# Dual_Power.net
KiCad netlist of a schematic drawn in Altium Designer
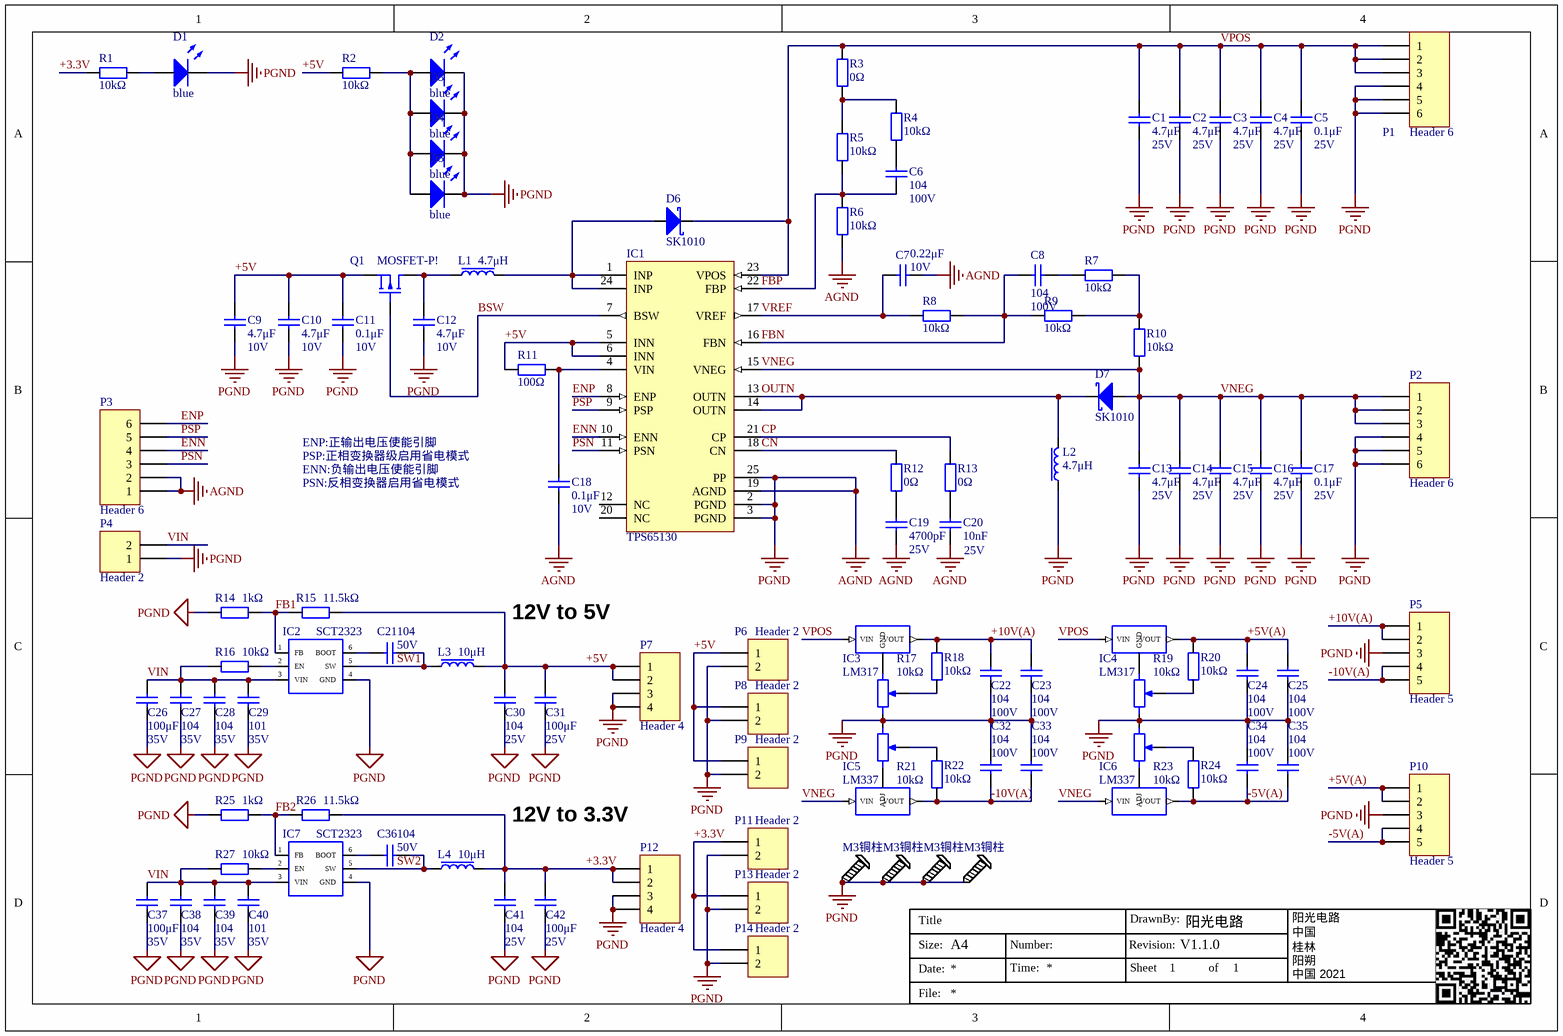
[diagram p0: Dual_Power.SchDoc]

(export (version "E")
  (design (tool "Eeschema 10.0.6"))
  (components
    (comp (ref "C1")
      (value "叠层陶瓷电容")
      (footprint "C0603")
      (description "无极性电容")
      (fields (field (name "CAPACITY") "4.7μF") (field (name "VOLTAGE") "25V"))
      (libsource (lib "原理图库") (part "104"))
    )
    (comp (ref "C2")
      (value "叠层陶瓷电容")
      (footprint "C0603")
      (description "无极性电容")
      (fields (field (name "CAPACITY") "4.7μF") (field (name "VOLTAGE") "25V"))
      (libsource (lib "原理图库") (part "104"))
    )
    (comp (ref "C3")
      (value "叠层陶瓷电容")
      (footprint "C0603")
      (description "无极性电容")
      (fields (field (name "CAPACITY") "4.7μF") (field (name "VOLTAGE") "25V"))
      (libsource (lib "原理图库") (part "104"))
    )
    (comp (ref "C4")
      (value "叠层陶瓷电容")
      (footprint "C0603")
      (description "无极性电容")
      (fields (field (name "CAPACITY") "4.7μF") (field (name "VOLTAGE") "25V"))
      (libsource (lib "原理图库") (part "104"))
    )
    (comp (ref "C5")
      (value "叠层陶瓷电容")
      (footprint "C0603")
      (description "无极性电容")
      (fields (field (name "CAPACITY") "0.1μF") (field (name "VOLTAGE") "25V"))
      (libsource (lib "原理图库") (part "104"))
    )
    (comp (ref "C6")
      (value "叠层陶瓷电容")
      (footprint "C0603")
      (description "无极性电容")
      (fields (field (name "CAPACITY") "104") (field (name "VOLTAGE") "100V"))
      (libsource (lib "原理图库") (part "104"))
    )
    (comp (ref "C7")
      (value "叠层陶瓷电容")
      (footprint "C0603")
      (description "无极性电容")
      (fields (field (name "CAPACITY") "0.22μF") (field (name "VOLTAGE") "10V"))
      (libsource (lib "原理图库") (part "104"))
    )
    (comp (ref "C8")
      (value "叠层陶瓷电容")
      (footprint "C0603")
      (description "无极性电容")
      (fields (field (name "CAPACITY") "104") (field (name "VOLTAGE") "100V"))
      (libsource (lib "原理图库") (part "104"))
    )
    (comp (ref "C9")
      (value "叠层陶瓷电容")
      (footprint "C0603")
      (description "无极性电容")
      (fields (field (name "CAPACITY") "4.7μF") (field (name "VOLTAGE") "10V"))
      (libsource (lib "原理图库") (part "104"))
    )
    (comp (ref "C10")
      (value "叠层陶瓷电容")
      (footprint "C0603")
      (description "无极性电容")
      (fields (field (name "CAPACITY") "4.7μF") (field (name "VOLTAGE") "10V"))
      (libsource (lib "原理图库") (part "104"))
    )
    (comp (ref "C11")
      (value "叠层陶瓷电容")
      (footprint "C0603")
      (description "无极性电容")
      (fields (field (name "CAPACITY") "0.1μF") (field (name "VOLTAGE") "10V"))
      (libsource (lib "原理图库") (part "104"))
    )
    (comp (ref "C12")
      (value "叠层陶瓷电容")
      (footprint "C0603")
      (description "无极性电容")
      (fields (field (name "CAPACITY") "4.7μF") (field (name "VOLTAGE") "10V"))
      (libsource (lib "原理图库") (part "104"))
    )
    (comp (ref "C13")
      (value "叠层陶瓷电容")
      (footprint "C0603")
      (description "无极性电容")
      (fields (field (name "CAPACITY") "4.7μF") (field (name "VOLTAGE") "25V"))
      (libsource (lib "原理图库") (part "104"))
    )
    (comp (ref "C14")
      (value "叠层陶瓷电容")
      (footprint "C0603")
      (description "无极性电容")
      (fields (field (name "CAPACITY") "4.7μF") (field (name "VOLTAGE") "25V"))
      (libsource (lib "原理图库") (part "104"))
    )
    (comp (ref "C15")
      (value "叠层陶瓷电容")
      (footprint "C0603")
      (description "无极性电容")
      (fields (field (name "CAPACITY") "4.7μF") (field (name "VOLTAGE") "25V"))
      (libsource (lib "原理图库") (part "104"))
    )
    (comp (ref "C16")
      (value "叠层陶瓷电容")
      (footprint "C0603")
      (description "无极性电容")
      (fields (field (name "CAPACITY") "4.7μF") (field (name "VOLTAGE") "25V"))
      (libsource (lib "原理图库") (part "104"))
    )
    (comp (ref "C17")
      (value "叠层陶瓷电容")
      (footprint "C0603")
      (description "无极性电容")
      (fields (field (name "CAPACITY") "0.1μF") (field (name "VOLTAGE") "25V"))
      (libsource (lib "原理图库") (part "104"))
    )
    (comp (ref "C18")
      (value "叠层陶瓷电容")
      (footprint "C0603")
      (description "无极性电容")
      (fields (field (name "CAPACITY") "0.1μF") (field (name "VOLTAGE") "10V"))
      (libsource (lib "原理图库") (part "104"))
    )
    (comp (ref "C19")
      (value "叠层陶瓷电容")
      (footprint "C0603")
      (description "无极性电容")
      (fields (field (name "CAPACITY") "4700pF") (field (name "VOLTAGE") "25V"))
      (libsource (lib "原理图库") (part "104"))
    )
    (comp (ref "C20")
      (value "叠层陶瓷电容")
      (footprint "C0603")
      (description "无极性电容")
      (fields (field (name "CAPACITY") "10nF") (field (name "VOLTAGE") "25V"))
      (libsource (lib "原理图库") (part "104"))
    )
    (comp (ref "C21")
      (value "叠层陶瓷电容")
      (footprint "C0603")
      (description "无极性电容")
      (fields (field (name "CAPACITY") "104") (field (name "VOLTAGE") "50V"))
      (libsource (lib "原理图库") (part "104"))
    )
    (comp (ref "C22")
      (value "叠层陶瓷电容")
      (footprint "C0603")
      (description "无极性电容")
      (fields (field (name "CAPACITY") "104") (field (name "VOLTAGE") "100V"))
      (libsource (lib "原理图库") (part "104"))
    )
    (comp (ref "C23")
      (value "叠层陶瓷电容")
      (footprint "C0603")
      (description "无极性电容")
      (fields (field (name "CAPACITY") "104") (field (name "VOLTAGE") "100V"))
      (libsource (lib "原理图库") (part "104"))
    )
    (comp (ref "C24")
      (value "叠层陶瓷电容")
      (footprint "C0603")
      (description "无极性电容")
      (fields (field (name "CAPACITY") "104") (field (name "VOLTAGE") "100V"))
      (libsource (lib "原理图库") (part "104"))
    )
    (comp (ref "C25")
      (value "叠层陶瓷电容")
      (footprint "C0603")
      (description "无极性电容")
      (fields (field (name "CAPACITY") "104") (field (name "VOLTAGE") "100V"))
      (libsource (lib "原理图库") (part "104"))
    )
    (comp (ref "C26")
      (value "叠层陶瓷电容")
      (footprint "C0603")
      (description "无极性电容")
      (fields (field (name "CAPACITY") "100μF") (field (name "VOLTAGE") "35V"))
      (libsource (lib "原理图库") (part "104"))
    )
    (comp (ref "C27")
      (value "叠层陶瓷电容")
      (footprint "C0603")
      (description "无极性电容")
      (fields (field (name "CAPACITY") "104") (field (name "VOLTAGE") "35V"))
      (libsource (lib "原理图库") (part "104"))
    )
    (comp (ref "C28")
      (value "叠层陶瓷电容")
      (footprint "C0603")
      (description "无极性电容")
      (fields (field (name "CAPACITY") "104") (field (name "VOLTAGE") "35V"))
      (libsource (lib "原理图库") (part "104"))
    )
    (comp (ref "C29")
      (value "叠层陶瓷电容")
      (footprint "C0603")
      (description "无极性电容")
      (fields (field (name "CAPACITY") "101") (field (name "VOLTAGE") "35V"))
      (libsource (lib "原理图库") (part "104"))
    )
    (comp (ref "C30")
      (value "叠层陶瓷电容")
      (footprint "C0603")
      (description "无极性电容")
      (fields (field (name "CAPACITY") "104") (field (name "VOLTAGE") "25V"))
      (libsource (lib "原理图库") (part "104"))
    )
    (comp (ref "C31")
      (value "叠层陶瓷电容")
      (footprint "C0603")
      (description "无极性电容")
      (fields (field (name "CAPACITY") "100μF") (field (name "VOLTAGE") "25V"))
      (libsource (lib "原理图库") (part "104"))
    )
    (comp (ref "C32")
      (value "叠层陶瓷电容")
      (footprint "C0603")
      (description "无极性电容")
      (fields (field (name "CAPACITY") "104") (field (name "VOLTAGE") "100V"))
      (libsource (lib "原理图库") (part "104"))
    )
    (comp (ref "C33")
      (value "叠层陶瓷电容")
      (footprint "C0603")
      (description "无极性电容")
      (fields (field (name "CAPACITY") "104") (field (name "VOLTAGE") "100V"))
      (libsource (lib "原理图库") (part "104"))
    )
    (comp (ref "C34")
      (value "叠层陶瓷电容")
      (footprint "C0603")
      (description "无极性电容")
      (fields (field (name "CAPACITY") "104") (field (name "VOLTAGE") "100V"))
      (libsource (lib "原理图库") (part "104"))
    )
    (comp (ref "C35")
      (value "叠层陶瓷电容")
      (footprint "C0603")
      (description "无极性电容")
      (fields (field (name "CAPACITY") "104") (field (name "VOLTAGE") "100V"))
      (libsource (lib "原理图库") (part "104"))
    )
    (comp (ref "C36")
      (value "叠层陶瓷电容")
      (footprint "C0603")
      (description "无极性电容")
      (fields (field (name "CAPACITY") "104") (field (name "VOLTAGE") "50V"))
      (libsource (lib "原理图库") (part "104"))
    )
    (comp (ref "C37")
      (value "叠层陶瓷电容")
      (footprint "C0603")
      (description "无极性电容")
      (fields (field (name "CAPACITY") "100μF") (field (name "VOLTAGE") "35V"))
      (libsource (lib "原理图库") (part "104"))
    )
    (comp (ref "C38")
      (value "叠层陶瓷电容")
      (footprint "C0603")
      (description "无极性电容")
      (fields (field (name "CAPACITY") "104") (field (name "VOLTAGE") "35V"))
      (libsource (lib "原理图库") (part "104"))
    )
    (comp (ref "C39")
      (value "叠层陶瓷电容")
      (footprint "C0603")
      (description "无极性电容")
      (fields (field (name "CAPACITY") "104") (field (name "VOLTAGE") "35V"))
      (libsource (lib "原理图库") (part "104"))
    )
    (comp (ref "C40")
      (value "叠层陶瓷电容")
      (footprint "C0603")
      (description "无极性电容")
      (fields (field (name "CAPACITY") "101") (field (name "VOLTAGE") "35V"))
      (libsource (lib "原理图库") (part "104"))
    )
    (comp (ref "C41")
      (value "叠层陶瓷电容")
      (footprint "C0603")
      (description "无极性电容")
      (fields (field (name "CAPACITY") "104") (field (name "VOLTAGE") "25V"))
      (libsource (lib "原理图库") (part "104"))
    )
    (comp (ref "C42")
      (value "叠层陶瓷电容")
      (footprint "C0603")
      (description "无极性电容")
      (fields (field (name "CAPACITY") "100μF") (field (name "VOLTAGE") "25V"))
      (libsource (lib "原理图库") (part "104"))
    )
    (comp (ref "D1")
      (value "LED")
      (footprint "LED 0603")
      (fields (field (name "TYPE") "blue"))
      (libsource (lib "原理图库") (part "LED"))
    )
    (comp (ref "D2")
      (value "LED")
      (footprint "LED 0603(反贴)")
      (fields (field (name "TYPE") "blue"))
      (libsource (lib "原理图库") (part "LED"))
    )
    (comp (ref "D3")
      (value "LED")
      (footprint "LED 0603(反贴)")
      (fields (field (name "TYPE") "blue"))
      (libsource (lib "原理图库") (part "LED"))
    )
    (comp (ref "D4")
      (value "LED")
      (footprint "LED 0603(反贴)")
      (fields (field (name "TYPE") "blue"))
      (libsource (lib "原理图库") (part "LED"))
    )
    (comp (ref "D5")
      (value "LED")
      (footprint "LED 0603(反贴)")
      (fields (field (name "TYPE") "blue"))
      (libsource (lib "原理图库") (part "LED"))
    )
    (comp (ref "D6")
      (value "SK1010")
      (footprint "SOD-523")
      (description "肖特基二极管")
      (libsource (lib "原理图库") (part "schottky(肖特基二极管)"))
    )
    (comp (ref "D7")
      (value "SK1010")
      (footprint "SOD-523")
      (description "肖特基二极管")
      (libsource (lib "原理图库") (part "schottky(肖特基二极管)"))
    )
    (comp (ref "IC1")
      (value "TPS65130")
      (footprint "VQFN-24")
      (description "boost双电源输出")
      (libsource (lib "原理图库") (part "TPS65130"))
    )
    (comp (ref "IC2")
      (value "DC-DC")
      (footprint "TSOT-23-6")
      (description "3.8V-32V 2A 同步降压DC-DC变换器")
      (fields (field (name "TYPE") "SCT2323"))
      (libsource (lib "原理图库") (part "SCT2320"))
    )
    (comp (ref "IC3")
      (value "LM317")
      (footprint "SOT-223")
      (description "线性稳压")
      (libsource (lib "原理图库") (part "LM317"))
    )
    (comp (ref "IC4")
      (value "LM317")
      (footprint "SOT-223")
      (description "线性稳压")
      (libsource (lib "原理图库") (part "LM317"))
    )
    (comp (ref "IC5")
      (value "LM337")
      (footprint "SOT-223")
      (description "负线性稳压")
      (libsource (lib "原理图库") (part "LM337"))
    )
    (comp (ref "IC6")
      (value "LM337")
      (footprint "SOT-223")
      (description "负线性稳压")
      (libsource (lib "原理图库") (part "LM337"))
    )
    (comp (ref "IC7")
      (value "DC-DC")
      (footprint "TSOT-23-6")
      (description "3.8V-32V 2A 同步降压DC-DC变换器")
      (fields (field (name "TYPE") "SCT2323"))
      (libsource (lib "原理图库") (part "SCT2320"))
    )
    (comp (ref "L1")
      (value "电感")
      (footprint "L0420")
      (fields (field (name "TYPE") "4.7μH"))
      (libsource (lib "原理图库") (part "470mH"))
    )
    (comp (ref "L2")
      (value "电感")
      (footprint "L0420")
      (fields (field (name "TYPE") "4.7μH"))
      (libsource (lib "原理图库") (part "470mH"))
    )
    (comp (ref "L3")
      (value "电感")
      (footprint "L0420")
      (fields (field (name "TYPE") "10μH"))
      (libsource (lib "原理图库") (part "470mH"))
    )
    (comp (ref "L4")
      (value "电感")
      (footprint "L0420")
      (fields (field (name "TYPE") "10μH"))
      (libsource (lib "原理图库") (part "470mH"))
    )
    (comp (ref "P1")
      (value "Header 6")
      (footprint "HDR1X6")
      (description "Header, 6-Pin")
      (libsource (lib "") (part "Header 6_1"))
    )
    (comp (ref "P2")
      (value "Header 6")
      (footprint "HDR1X6")
      (description "Header, 6-Pin")
      (libsource (lib "") (part "Header 6_1"))
    )
    (comp (ref "P3")
      (value "Header 6")
      (footprint "HDR1X6")
      (description "Header, 6-Pin")
      (libsource (lib "Miscellaneous Connectors") (part "Header 6"))
    )
    (comp (ref "P4")
      (value "Header 2")
      (footprint "XT30PW-M(母)")
      (description "Header, 2-Pin")
      (libsource (lib "") (part "Header 2_1"))
    )
    (comp (ref "P5")
      (value "Header 5")
      (footprint "HDR1X5")
      (description "Header, 5-Pin")
      (libsource (lib "Miscellaneous Connectors") (part "Header 5"))
    )
    (comp (ref "P6")
      (value "Header 2")
      (footprint "XH2.54-2P")
      (description "Header, 2-Pin")
      (fields (field (name "PUBLISHER") "Altium Limited"))
      (libsource (lib "Miscellaneous Connectors") (part "Header 2"))
    )
    (comp (ref "P7")
      (value "Header 4")
      (footprint "HDR1X4")
      (description "Header, 4-Pin")
      (libsource (lib "Miscellaneous Connectors") (part "Header 4"))
    )
    (comp (ref "P8")
      (value "Header 2")
      (footprint "XH2.54-2P")
      (description "Header, 2-Pin")
      (fields (field (name "PUBLISHER") "Altium Limited"))
      (libsource (lib "Miscellaneous Connectors") (part "Header 2"))
    )
    (comp (ref "P9")
      (value "Header 2")
      (footprint "XH2.54-2P")
      (description "Header, 2-Pin")
      (fields (field (name "PUBLISHER") "Altium Limited"))
      (libsource (lib "Miscellaneous Connectors") (part "Header 2"))
    )
    (comp (ref "P10")
      (value "Header 5")
      (footprint "HDR1X5")
      (description "Header, 5-Pin")
      (libsource (lib "Miscellaneous Connectors") (part "Header 5"))
    )
    (comp (ref "P11")
      (value "Header 2")
      (footprint "XH2.54-2P")
      (description "Header, 2-Pin")
      (fields (field (name "PUBLISHER") "Altium Limited"))
      (libsource (lib "Miscellaneous Connectors") (part "Header 2"))
    )
    (comp (ref "P12")
      (value "Header 4")
      (footprint "HDR1X4")
      (description "Header, 4-Pin")
      (libsource (lib "Miscellaneous Connectors") (part "Header 4"))
    )
    (comp (ref "P13")
      (value "Header 2")
      (footprint "XH2.54-2P")
      (description "Header, 2-Pin")
      (fields (field (name "PUBLISHER") "Altium Limited"))
      (libsource (lib "Miscellaneous Connectors") (part "Header 2"))
    )
    (comp (ref "P14")
      (value "Header 2")
      (footprint "XH2.54-2P")
      (description "Header, 2-Pin")
      (fields (field (name "PUBLISHER") "Altium Limited"))
      (libsource (lib "Miscellaneous Connectors") (part "Header 2"))
    )
    (comp (ref "Q1")
      (value "MOSFET-P!")
      (footprint "SOT-23")
      (description "场效应管")
      (libsource (lib "原理图库") (part "MOSFET-P!"))
    )
    (comp (ref "R1")
      (value "贴片电阻")
      (footprint "R0603")
      (description "贴片/直插电阻")
      (fields (field (name "RESISTANCE") "10kΩ"))
      (libsource (lib "原理图库") (part "10kΩ"))
    )
    (comp (ref "R2")
      (value "贴片电阻")
      (footprint "R0603")
      (description "贴片/直插电阻")
      (fields (field (name "RESISTANCE") "10kΩ"))
      (libsource (lib "原理图库") (part "10kΩ"))
    )
    (comp (ref "R3")
      (value "贴片电阻")
      (footprint "R0603")
      (description "贴片/直插电阻")
      (fields (field (name "RESISTANCE") "0Ω"))
      (libsource (lib "原理图库") (part "10kΩ"))
    )
    (comp (ref "R4")
      (value "贴片电阻")
      (footprint "R0603")
      (description "贴片/直插电阻")
      (fields (field (name "RESISTANCE") "10kΩ"))
      (libsource (lib "原理图库") (part "10kΩ"))
    )
    (comp (ref "R5")
      (value "贴片电阻")
      (footprint "R0603")
      (description "贴片/直插电阻")
      (fields (field (name "RESISTANCE") "10kΩ"))
      (libsource (lib "原理图库") (part "10kΩ"))
    )
    (comp (ref "R6")
      (value "贴片电阻")
      (footprint "R0603")
      (description "贴片/直插电阻")
      (fields (field (name "RESISTANCE") "10kΩ"))
      (libsource (lib "原理图库") (part "10kΩ"))
    )
    (comp (ref "R7")
      (value "贴片电阻")
      (footprint "R0603")
      (description "贴片/直插电阻")
      (fields (field (name "RESISTANCE") "10kΩ"))
      (libsource (lib "原理图库") (part "10kΩ"))
    )
    (comp (ref "R8")
      (value "贴片电阻")
      (footprint "R0603")
      (description "贴片/直插电阻")
      (fields (field (name "RESISTANCE") "10kΩ"))
      (libsource (lib "原理图库") (part "10kΩ"))
    )
    (comp (ref "R9")
      (value "贴片电阻")
      (footprint "R0603")
      (description "贴片/直插电阻")
      (fields (field (name "RESISTANCE") "10kΩ"))
      (libsource (lib "原理图库") (part "10kΩ"))
    )
    (comp (ref "R10")
      (value "贴片电阻")
      (footprint "R0603")
      (description "贴片/直插电阻")
      (fields (field (name "RESISTANCE") "10kΩ"))
      (libsource (lib "原理图库") (part "10kΩ"))
    )
    (comp (ref "R11")
      (value "贴片电阻")
      (footprint "R0603")
      (description "贴片/直插电阻")
      (fields (field (name "RESISTANCE") "100Ω"))
      (libsource (lib "原理图库") (part "10kΩ"))
    )
    (comp (ref "R12")
      (value "贴片电阻")
      (footprint "R0603")
      (description "贴片/直插电阻")
      (fields (field (name "RESISTANCE") "0Ω"))
      (libsource (lib "原理图库") (part "10kΩ"))
    )
    (comp (ref "R13")
      (value "贴片电阻")
      (footprint "R0603")
      (description "贴片/直插电阻")
      (fields (field (name "RESISTANCE") "0Ω"))
      (libsource (lib "原理图库") (part "10kΩ"))
    )
    (comp (ref "R14")
      (value "贴片电阻")
      (footprint "R0603")
      (description "贴片/直插电阻")
      (fields (field (name "RESISTANCE") "1kΩ"))
      (libsource (lib "原理图库") (part "10kΩ"))
    )
    (comp (ref "R15")
      (value "贴片电阻")
      (footprint "R0603")
      (description "贴片/直插电阻")
      (fields (field (name "RESISTANCE") "11.5kΩ"))
      (libsource (lib "原理图库") (part "10kΩ"))
    )
    (comp (ref "R16")
      (value "贴片电阻")
      (footprint "R0603")
      (description "贴片/直插电阻")
      (fields (field (name "RESISTANCE") "10kΩ"))
      (libsource (lib "原理图库") (part "10kΩ"))
    )
    (comp (ref "R17")
      (value "10kΩ")
      (footprint "3296W-103")
      (description "三脚可调式电位器")
      (libsource (lib "原理图库") (part "100kΩ"))
    )
    (comp (ref "R18")
      (value "贴片电阻")
      (footprint "R0603")
      (description "贴片/直插电阻")
      (fields (field (name "RESISTANCE") "10kΩ"))
      (libsource (lib "原理图库") (part "10kΩ"))
    )
    (comp (ref "R19")
      (value "10kΩ")
      (footprint "3296W-103")
      (description "三脚可调式电位器")
      (libsource (lib "原理图库") (part "100kΩ"))
    )
    (comp (ref "R20")
      (value "贴片电阻")
      (footprint "R0603")
      (description "贴片/直插电阻")
      (fields (field (name "RESISTANCE") "10kΩ"))
      (libsource (lib "原理图库") (part "10kΩ"))
    )
    (comp (ref "R21")
      (value "10kΩ")
      (footprint "3296W-103")
      (description "三脚可调式电位器")
      (libsource (lib "原理图库") (part "100kΩ"))
    )
    (comp (ref "R22")
      (value "贴片电阻")
      (footprint "R0603")
      (description "贴片/直插电阻")
      (fields (field (name "RESISTANCE") "10kΩ"))
      (libsource (lib "原理图库") (part "10kΩ"))
    )
    (comp (ref "R23")
      (value "10kΩ")
      (footprint "3296W-103")
      (description "三脚可调式电位器")
      (libsource (lib "原理图库") (part "100kΩ"))
    )
    (comp (ref "R24")
      (value "贴片电阻")
      (footprint "R0603")
      (description "贴片/直插电阻")
      (fields (field (name "RESISTANCE") "10kΩ"))
      (libsource (lib "原理图库") (part "10kΩ"))
    )
    (comp (ref "R25")
      (value "贴片电阻")
      (footprint "R0603")
      (description "贴片/直插电阻")
      (fields (field (name "RESISTANCE") "1kΩ"))
      (libsource (lib "原理图库") (part "10kΩ"))
    )
    (comp (ref "R26")
      (value "贴片电阻")
      (footprint "R0603")
      (description "贴片/直插电阻")
      (fields (field (name "RESISTANCE") "11.5kΩ"))
      (libsource (lib "原理图库") (part "10kΩ"))
    )
    (comp (ref "R27")
      (value "贴片电阻")
      (footprint "R0603")
      (description "贴片/直插电阻")
      (fields (field (name "RESISTANCE") "10kΩ"))
      (libsource (lib "原理图库") (part "10kΩ"))
    )
    (comp (ref "S1") (value "M3铜柱") (footprint "M3") (libsource (lib "原理图库") (part "M3铜柱")))
    (comp (ref "S2") (value "M3铜柱") (footprint "M3") (libsource (lib "原理图库") (part "M3铜柱")))
    (comp (ref "S3") (value "M3铜柱") (footprint "M3") (libsource (lib "原理图库") (part "M3铜柱")))
    (comp (ref "S4") (value "M3铜柱") (footprint "M3") (libsource (lib "原理图库") (part "M3铜柱")))
  )
  (nets
    (net (code "1") (name "/+3.3V") (class "Default")
      (node (ref "C41") (pin "2") (pintype "passive"))
      (node (ref "C42") (pin "2") (pintype "passive"))
      (node (ref "L4") (pin "1") (pintype "passive"))
      (node (ref "P11") (pin "1") (pinfunction "1_1") (pintype "passive"))
      (node (ref "P12") (pin "1") (pinfunction "1_1") (pintype "passive"))
      (node (ref "P12") (pin "2") (pinfunction "2_2") (pintype "passive"))
      (node (ref "P13") (pin "1") (pinfunction "1_1") (pintype "passive"))
      (node (ref "P14") (pin "1") (pinfunction "1_1") (pintype "passive"))
      (node (ref "R1") (pin "1") (pintype "passive"))
      (node (ref "R26") (pin "2") (pintype "passive"))
    )
    (net (code "2") (name "/+5V") (class "Default")
      (node (ref "C10") (pin "2") (pintype "passive"))
      (node (ref "C11") (pin "2") (pintype "passive"))
      (node (ref "C30") (pin "2") (pintype "passive"))
      (node (ref "C31") (pin "2") (pintype "passive"))
      (node (ref "C9") (pin "2") (pintype "passive"))
      (node (ref "IC1") (pin "5") (pinfunction "INN_5") (pintype "power_in"))
      (node (ref "IC1") (pin "6") (pinfunction "INN_6") (pintype "power_in"))
      (node (ref "L3") (pin "1") (pintype "passive"))
      (node (ref "P6") (pin "1") (pinfunction "1_1") (pintype "passive"))
      (node (ref "P7") (pin "1") (pinfunction "1_1") (pintype "passive"))
      (node (ref "P7") (pin "2") (pinfunction "2_2") (pintype "passive"))
      (node (ref "P8") (pin "1") (pinfunction "1_1") (pintype "passive"))
      (node (ref "P9") (pin "1") (pinfunction "1_1") (pintype "passive"))
      (node (ref "Q1") (pin "3") (pinfunction "S_3") (pintype "passive"))
      (node (ref "R11") (pin "1") (pintype "passive"))
      (node (ref "R15") (pin "2") (pintype "passive"))
      (node (ref "R2") (pin "1") (pintype "passive"))
    )
    (net (code "3") (name "/+5V(A)") (class "Default")
      (node (ref "C24") (pin "2") (pintype "passive"))
      (node (ref "C25") (pin "2") (pintype "passive"))
      (node (ref "IC4") (pin "2") (pinfunction "VOUT_2") (pintype "output"))
      (node (ref "P10") (pin "1") (pinfunction "1_1") (pintype "passive"))
      (node (ref "P10") (pin "2") (pinfunction "2_2") (pintype "passive"))
      (node (ref "R20") (pin "2") (pintype "passive"))
    )
    (net (code "4") (name "/+10V(A)") (class "Default")
      (node (ref "C22") (pin "2") (pintype "passive"))
      (node (ref "C23") (pin "2") (pintype "passive"))
      (node (ref "IC3") (pin "2") (pinfunction "VOUT_2") (pintype "output"))
      (node (ref "P5") (pin "1") (pinfunction "1_1") (pintype "passive"))
      (node (ref "P5") (pin "2") (pinfunction "2_2") (pintype "passive"))
      (node (ref "R18") (pin "2") (pintype "passive"))
    )
    (net (code "5") (name "/-5V(A)") (class "Default")
      (node (ref "C34") (pin "1") (pintype "passive"))
      (node (ref "C35") (pin "1") (pintype "passive"))
      (node (ref "IC6") (pin "3") (pinfunction "VOUT_3") (pintype "output"))
      (node (ref "P10") (pin "4") (pinfunction "4_4") (pintype "passive"))
      (node (ref "P10") (pin "5") (pinfunction "5_5") (pintype "passive"))
      (node (ref "R24") (pin "1") (pintype "passive"))
    )
    (net (code "6") (name "/-10V(A)") (class "Default")
      (node (ref "C32") (pin "1") (pintype "passive"))
      (node (ref "C33") (pin "1") (pintype "passive"))
      (node (ref "IC5") (pin "3") (pinfunction "VOUT_3") (pintype "output"))
      (node (ref "P5") (pin "4") (pinfunction "4_4") (pintype "passive"))
      (node (ref "P5") (pin "5") (pinfunction "5_5") (pintype "passive"))
      (node (ref "R22") (pin "1") (pintype "passive"))
    )
    (net (code "7") (name "/BSW") (class "Default")
      (node (ref "IC1") (pin "7") (pinfunction "BSW_7") (pintype "output"))
      (node (ref "Q1") (pin "1") (pinfunction "G_1") (pintype "passive"))
    )
    (net (code "8") (name "/CN") (class "Default")
      (node (ref "IC1") (pin "18") (pinfunction "CN_18") (pintype "passive"))
      (node (ref "R12") (pin "2") (pintype "passive"))
    )
    (net (code "9") (name "/CP") (class "Default")
      (node (ref "IC1") (pin "21") (pinfunction "CP_21") (pintype "passive"))
      (node (ref "R13") (pin "2") (pintype "passive"))
    )
    (net (code "10") (name "/ENN") (class "Default")
      (node (ref "IC1") (pin "10") (pinfunction "ENN_10") (pintype "input"))
      (node (ref "P3") (pin "4") (pinfunction "4_4") (pintype "passive"))
    )
    (net (code "11") (name "/ENP") (class "Default")
      (node (ref "IC1") (pin "8") (pinfunction "ENP_8") (pintype "input"))
      (node (ref "P3") (pin "6") (pinfunction "6_6") (pintype "passive"))
    )
    (net (code "12") (name "/FB1") (class "Default")
      (node (ref "IC2") (pin "1") (pinfunction "FB_1") (pintype "passive"))
      (node (ref "R14") (pin "2") (pintype "passive"))
      (node (ref "R15") (pin "1") (pintype "passive"))
    )
    (net (code "13") (name "/FB2") (class "Default")
      (node (ref "IC7") (pin "1") (pinfunction "FB_1") (pintype "passive"))
      (node (ref "R25") (pin "2") (pintype "passive"))
      (node (ref "R26") (pin "1") (pintype "passive"))
    )
    (net (code "14") (name "/FBN") (class "Default")
      (node (ref "C8") (pin "1") (pintype "passive"))
      (node (ref "IC1") (pin "16") (pinfunction "FBN_16") (pintype "input"))
      (node (ref "R8") (pin "2") (pintype "passive"))
      (node (ref "R9") (pin "1") (pintype "passive"))
    )
    (net (code "15") (name "/FBP") (class "Default")
      (node (ref "C6") (pin "1") (pintype "passive"))
      (node (ref "IC1") (pin "22") (pinfunction "FBP_22") (pintype "input"))
      (node (ref "R5") (pin "1") (pintype "passive"))
      (node (ref "R6") (pin "2") (pintype "passive"))
    )
    (net (code "16") (name "/OUTN") (class "Default")
      (node (ref "D7") (pin "2") (pinfunction "K_2") (pintype "passive"))
      (node (ref "IC1") (pin "13") (pinfunction "OUTN_13") (pintype "power_in"))
      (node (ref "IC1") (pin "14") (pinfunction "OUTN_14") (pintype "power_in"))
      (node (ref "L2") (pin "1") (pintype "passive"))
    )
    (net (code "17") (name "/PSN") (class "Default")
      (node (ref "IC1") (pin "11") (pinfunction "PSN_11") (pintype "input"))
      (node (ref "P3") (pin "3") (pinfunction "3_3") (pintype "passive"))
    )
    (net (code "18") (name "/PSP") (class "Default")
      (node (ref "IC1") (pin "9") (pinfunction "PSP_9") (pintype "input"))
      (node (ref "P3") (pin "5") (pinfunction "5_5") (pintype "passive"))
    )
    (net (code "19") (name "/SW1") (class "Default")
      (node (ref "C21") (pin "2") (pintype "passive"))
      (node (ref "IC2") (pin "5") (pinfunction "SW_5") (pintype "passive"))
      (node (ref "L3") (pin "2") (pintype "passive"))
    )
    (net (code "20") (name "/SW2") (class "Default")
      (node (ref "C36") (pin "2") (pintype "passive"))
      (node (ref "IC7") (pin "5") (pinfunction "SW_5") (pintype "passive"))
      (node (ref "L4") (pin "2") (pintype "passive"))
    )
    (net (code "21") (name "/VIN") (class "Default")
      (node (ref "C26") (pin "2") (pintype "passive"))
      (node (ref "C27") (pin "2") (pintype "passive"))
      (node (ref "C28") (pin "2") (pintype "passive"))
      (node (ref "C29") (pin "2") (pintype "passive"))
      (node (ref "C37") (pin "2") (pintype "passive"))
      (node (ref "C38") (pin "2") (pintype "passive"))
      (node (ref "C39") (pin "2") (pintype "passive"))
      (node (ref "C40") (pin "2") (pintype "passive"))
      (node (ref "IC2") (pin "3") (pinfunction "VIN_3") (pintype "passive"))
      (node (ref "IC7") (pin "3") (pinfunction "VIN_3") (pintype "passive"))
      (node (ref "P4") (pin "2") (pinfunction "2_2") (pintype "passive"))
      (node (ref "R16") (pin "1") (pintype "passive"))
      (node (ref "R27") (pin "1") (pintype "passive"))
    )
    (net (code "22") (name "/VNEG") (class "Default")
      (node (ref "C13") (pin "2") (pintype "passive"))
      (node (ref "C14") (pin "2") (pintype "passive"))
      (node (ref "C15") (pin "2") (pintype "passive"))
      (node (ref "C16") (pin "2") (pintype "passive"))
      (node (ref "C17") (pin "2") (pintype "passive"))
      (node (ref "D7") (pin "1") (pinfunction "A_1") (pintype "passive"))
      (node (ref "IC1") (pin "15") (pinfunction "VNEG_15") (pintype "input"))
      (node (ref "IC5") (pin "2") (pinfunction "VIN_2") (pintype "input"))
      (node (ref "IC6") (pin "2") (pinfunction "VIN_2") (pintype "input"))
      (node (ref "P2") (pin "1") (pinfunction "1_1") (pintype "passive"))
      (node (ref "P2") (pin "2") (pinfunction "2_2") (pintype "passive"))
      (node (ref "P2") (pin "3") (pinfunction "3_3") (pintype "passive"))
      (node (ref "R10") (pin "1") (pintype "passive"))
    )
    (net (code "23") (name "/VPOS") (class "Default")
      (node (ref "C1") (pin "2") (pintype "passive"))
      (node (ref "C2") (pin "2") (pintype "passive"))
      (node (ref "C3") (pin "2") (pintype "passive"))
      (node (ref "C4") (pin "2") (pintype "passive"))
      (node (ref "C5") (pin "2") (pintype "passive"))
      (node (ref "D6") (pin "2") (pinfunction "K_2") (pintype "passive"))
      (node (ref "IC1") (pin "23") (pinfunction "VPOS_23") (pintype "input"))
      (node (ref "IC3") (pin "3") (pinfunction "VIN_3") (pintype "input"))
      (node (ref "IC4") (pin "3") (pinfunction "VIN_3") (pintype "input"))
      (node (ref "P1") (pin "1") (pinfunction "1_1") (pintype "passive"))
      (node (ref "P1") (pin "2") (pinfunction "2_2") (pintype "passive"))
      (node (ref "P1") (pin "3") (pinfunction "3_3") (pintype "passive"))
      (node (ref "R3") (pin "2") (pintype "passive"))
    )
    (net (code "24") (name "/VREF") (class "Default")
      (node (ref "C7") (pin "1") (pintype "passive"))
      (node (ref "IC1") (pin "17") (pinfunction "VREF_17") (pintype "output"))
      (node (ref "R8") (pin "1") (pintype "passive"))
    )
    (net (code "25") (name "AGND") (class "Default")
      (node (ref "C1") (pin "1") (pintype "passive"))
      (node (ref "C10") (pin "1") (pintype "passive"))
      (node (ref "C11") (pin "1") (pintype "passive"))
      (node (ref "C12") (pin "1") (pintype "passive"))
      (node (ref "C13") (pin "1") (pintype "passive"))
      (node (ref "C14") (pin "1") (pintype "passive"))
      (node (ref "C15") (pin "1") (pintype "passive"))
      (node (ref "C16") (pin "1") (pintype "passive"))
      (node (ref "C17") (pin "1") (pintype "passive"))
      (node (ref "C18") (pin "1") (pintype "passive"))
      (node (ref "C19") (pin "1") (pintype "passive"))
      (node (ref "C2") (pin "1") (pintype "passive"))
      (node (ref "C20") (pin "1") (pintype "passive"))
      (node (ref "C22") (pin "1") (pintype "passive"))
      (node (ref "C23") (pin "1") (pintype "passive"))
      (node (ref "C24") (pin "1") (pintype "passive"))
      (node (ref "C25") (pin "1") (pintype "passive"))
      (node (ref "C26") (pin "1") (pintype "passive"))
      (node (ref "C27") (pin "1") (pintype "passive"))
      (node (ref "C28") (pin "1") (pintype "passive"))
      (node (ref "C29") (pin "1") (pintype "passive"))
      (node (ref "C3") (pin "1") (pintype "passive"))
      (node (ref "C30") (pin "1") (pintype "passive"))
      (node (ref "C31") (pin "1") (pintype "passive"))
      (node (ref "C32") (pin "2") (pintype "passive"))
      (node (ref "C33") (pin "2") (pintype "passive"))
      (node (ref "C34") (pin "2") (pintype "passive"))
      (node (ref "C35") (pin "2") (pintype "passive"))
      (node (ref "C37") (pin "1") (pintype "passive"))
      (node (ref "C38") (pin "1") (pintype "passive"))
      (node (ref "C39") (pin "1") (pintype "passive"))
      (node (ref "C4") (pin "1") (pintype "passive"))
      (node (ref "C40") (pin "1") (pintype "passive"))
      (node (ref "C41") (pin "1") (pintype "passive"))
      (node (ref "C42") (pin "1") (pintype "passive"))
      (node (ref "C5") (pin "1") (pintype "passive"))
      (node (ref "C7") (pin "2") (pintype "passive"))
      (node (ref "C9") (pin "1") (pintype "passive"))
      (node (ref "D1") (pin "2") (pinfunction "K_2") (pintype "passive"))
      (node (ref "D2") (pin "2") (pinfunction "K_2") (pintype "passive"))
      (node (ref "D3") (pin "2") (pinfunction "K_2") (pintype "passive"))
      (node (ref "D4") (pin "2") (pinfunction "K_2") (pintype "passive"))
      (node (ref "D5") (pin "2") (pinfunction "K_2") (pintype "passive"))
      (node (ref "IC1") (pin "19") (pinfunction "AGND_19") (pintype "power_in"))
      (node (ref "IC1") (pin "2") (pinfunction "PGND_2") (pintype "power_in"))
      (node (ref "IC1") (pin "25") (pinfunction "PP_25") (pintype "power_in"))
      (node (ref "IC1") (pin "3") (pinfunction "PGND_3") (pintype "power_in"))
      (node (ref "IC2") (pin "4") (pinfunction "GND_4") (pintype "passive"))
      (node (ref "IC7") (pin "4") (pinfunction "GND_4") (pintype "passive"))
      (node (ref "L2") (pin "2") (pintype "passive"))
      (node (ref "P1") (pin "4") (pinfunction "4_4") (pintype "passive"))
      (node (ref "P1") (pin "5") (pinfunction "5_5") (pintype "passive"))
      (node (ref "P1") (pin "6") (pinfunction "6_6") (pintype "passive"))
      (node (ref "P10") (pin "3") (pinfunction "3_3") (pintype "passive"))
      (node (ref "P11") (pin "2") (pinfunction "2_2") (pintype "passive"))
      (node (ref "P12") (pin "3") (pinfunction "3_3") (pintype "passive"))
      (node (ref "P12") (pin "4") (pinfunction "4_4") (pintype "passive"))
      (node (ref "P13") (pin "2") (pinfunction "2_2") (pintype "passive"))
      (node (ref "P14") (pin "2") (pinfunction "2_2") (pintype "passive"))
      (node (ref "P2") (pin "4") (pinfunction "4_4") (pintype "passive"))
      (node (ref "P2") (pin "5") (pinfunction "5_5") (pintype "passive"))
      (node (ref "P2") (pin "6") (pinfunction "6_6") (pintype "passive"))
      (node (ref "P3") (pin "1") (pinfunction "1_1") (pintype "passive"))
      (node (ref "P3") (pin "2") (pinfunction "2_2") (pintype "passive"))
      (node (ref "P4") (pin "1") (pinfunction "1_1") (pintype "passive"))
      (node (ref "P5") (pin "3") (pinfunction "3_3") (pintype "passive"))
      (node (ref "P6") (pin "2") (pinfunction "2_2") (pintype "passive"))
      (node (ref "P7") (pin "3") (pinfunction "3_3") (pintype "passive"))
      (node (ref "P7") (pin "4") (pinfunction "4_4") (pintype "passive"))
      (node (ref "P8") (pin "2") (pinfunction "2_2") (pintype "passive"))
      (node (ref "P9") (pin "2") (pinfunction "2_2") (pintype "passive"))
      (node (ref "R14") (pin "1") (pintype "passive"))
      (node (ref "R17") (pin "1") (pinfunction "1_1") (pintype "passive"))
      (node (ref "R19") (pin "1") (pinfunction "1_1") (pintype "passive"))
      (node (ref "R21") (pin "3") (pinfunction "3_3") (pintype "passive"))
      (node (ref "R23") (pin "3") (pinfunction "3_3") (pintype "passive"))
      (node (ref "R25") (pin "1") (pintype "passive"))
      (node (ref "R6") (pin "1") (pintype "passive"))
      (node (ref "S1") (pin "1") (pinfunction "GND_1") (pintype "passive"))
      (node (ref "S2") (pin "1") (pinfunction "GND_1") (pintype "passive"))
      (node (ref "S3") (pin "1") (pinfunction "GND_1") (pintype "passive"))
      (node (ref "S4") (pin "1") (pinfunction "GND_1") (pintype "passive"))
    )
    (net (code "26") (name "Net-(C6-Pad2)") (class "Default")
      (node (ref "C6") (pin "2") (pintype "passive"))
      (node (ref "R4") (pin "1") (pintype "passive"))
    )
    (net (code "27") (name "Net-(C8-Pad2)") (class "Default")
      (node (ref "C8") (pin "2") (pintype "passive"))
      (node (ref "R7") (pin "1") (pintype "passive"))
    )
    (net (code "28") (name "Net-(C19-Pad2)") (class "Default")
      (node (ref "C19") (pin "2") (pintype "passive"))
      (node (ref "R12") (pin "1") (pintype "passive"))
    )
    (net (code "29") (name "Net-(C20-Pad2)") (class "Default")
      (node (ref "C20") (pin "2") (pintype "passive"))
      (node (ref "R13") (pin "1") (pintype "passive"))
    )
    (net (code "30") (name "Net-(D1-A)") (class "Default")
      (node (ref "D1") (pin "1") (pinfunction "A_1") (pintype "passive"))
      (node (ref "R1") (pin "2") (pintype "passive"))
    )
    (net (code "31") (name "Net-(D2-A)") (class "Default")
      (node (ref "D2") (pin "1") (pinfunction "A_1") (pintype "passive"))
      (node (ref "D3") (pin "1") (pinfunction "A_1") (pintype "passive"))
      (node (ref "D4") (pin "1") (pinfunction "A_1") (pintype "passive"))
      (node (ref "D5") (pin "1") (pinfunction "A_1") (pintype "passive"))
      (node (ref "R2") (pin "2") (pintype "passive"))
    )
    (net (code "32") (name "Net-(D6-A)") (class "Default")
      (node (ref "D6") (pin "1") (pinfunction "A_1") (pintype "passive"))
      (node (ref "IC1") (pin "1") (pinfunction "INP_1") (pintype "power_in"))
      (node (ref "IC1") (pin "24") (pinfunction "INP_24") (pintype "power_in"))
      (node (ref "L1") (pin "1") (pintype "passive"))
    )
    (net (code "33") (name "Net-(IC1-VIN)") (class "Default")
      (node (ref "C18") (pin "2") (pintype "passive"))
      (node (ref "IC1") (pin "4") (pinfunction "VIN_4") (pintype "power_in"))
      (node (ref "R11") (pin "2") (pintype "passive"))
    )
    (net (code "34") (name "Net-(IC2-BOOT)") (class "Default")
      (node (ref "C21") (pin "1") (pintype "passive"))
      (node (ref "IC2") (pin "6") (pinfunction "BOOT_6") (pintype "passive"))
    )
    (net (code "35") (name "Net-(IC2-EN)") (class "Default")
      (node (ref "IC2") (pin "2") (pinfunction "EN_2") (pintype "passive"))
      (node (ref "R16") (pin "2") (pintype "passive"))
    )
    (net (code "36") (name "Net-(IC3-GND)") (class "Default")
      (node (ref "IC3") (pin "1") (pinfunction "GND_1") (pintype "passive"))
      (node (ref "R17") (pin "3") (pinfunction "3_3") (pintype "passive"))
    )
    (net (code "37") (name "Net-(IC4-GND)") (class "Default")
      (node (ref "IC4") (pin "1") (pinfunction "GND_1") (pintype "passive"))
      (node (ref "R19") (pin "3") (pinfunction "3_3") (pintype "passive"))
    )
    (net (code "38") (name "Net-(IC5-ADJ)") (class "Default")
      (node (ref "IC5") (pin "1") (pinfunction "ADJ_1") (pintype "passive"))
      (node (ref "R21") (pin "1") (pinfunction "1_1") (pintype "passive"))
    )
    (net (code "39") (name "Net-(IC6-ADJ)") (class "Default")
      (node (ref "IC6") (pin "1") (pinfunction "ADJ_1") (pintype "passive"))
      (node (ref "R23") (pin "1") (pinfunction "1_1") (pintype "passive"))
    )
    (net (code "40") (name "Net-(IC7-BOOT)") (class "Default")
      (node (ref "C36") (pin "1") (pintype "passive"))
      (node (ref "IC7") (pin "6") (pinfunction "BOOT_6") (pintype "passive"))
    )
    (net (code "41") (name "Net-(IC7-EN)") (class "Default")
      (node (ref "IC7") (pin "2") (pinfunction "EN_2") (pintype "passive"))
      (node (ref "R27") (pin "2") (pintype "passive"))
    )
    (net (code "42") (name "Net-(Q1-D)") (class "Default")
      (node (ref "C12") (pin "2") (pintype "passive"))
      (node (ref "L1") (pin "2") (pintype "passive"))
      (node (ref "Q1") (pin "2") (pinfunction "D_2") (pintype "passive"))
    )
    (net (code "43") (name "Net-(R3-Pad1)") (class "Default")
      (node (ref "R3") (pin "1") (pintype "passive"))
      (node (ref "R4") (pin "2") (pintype "passive"))
      (node (ref "R5") (pin "2") (pintype "passive"))
    )
    (net (code "44") (name "Net-(R10-Pad2)") (class "Default")
      (node (ref "R10") (pin "2") (pintype "passive"))
      (node (ref "R7") (pin "2") (pintype "passive"))
      (node (ref "R9") (pin "2") (pintype "passive"))
    )
    (net (code "45") (name "Net-(R17-Pad2)") (class "Default")
      (node (ref "R17") (pin "2") (pinfunction "2_2") (pintype "passive"))
      (node (ref "R18") (pin "1") (pintype "passive"))
    )
    (net (code "46") (name "Net-(R19-Pad2)") (class "Default")
      (node (ref "R19") (pin "2") (pinfunction "2_2") (pintype "passive"))
      (node (ref "R20") (pin "1") (pintype "passive"))
    )
    (net (code "47") (name "Net-(R21-Pad2)") (class "Default")
      (node (ref "R21") (pin "2") (pinfunction "2_2") (pintype "passive"))
      (node (ref "R22") (pin "2") (pintype "passive"))
    )
    (net (code "48") (name "Net-(R23-Pad2)") (class "Default")
      (node (ref "R23") (pin "2") (pinfunction "2_2") (pintype "passive"))
      (node (ref "R24") (pin "2") (pintype "passive"))
    )
    (net (code "49") (name "unconnected-(IC1-NC-Pad12)") (class "Default")
      (node (ref "IC1") (pin "12") (pinfunction "NC_12") (pintype "passive"))
    )
    (net (code "50") (name "unconnected-(IC1-NC-Pad20)") (class "Default")
      (node (ref "IC1") (pin "20") (pinfunction "NC_20") (pintype "passive"))
    )
  )
)
